# RS232_HIN232.net
KiCad netlist of a schematic drawn in Altium Designer
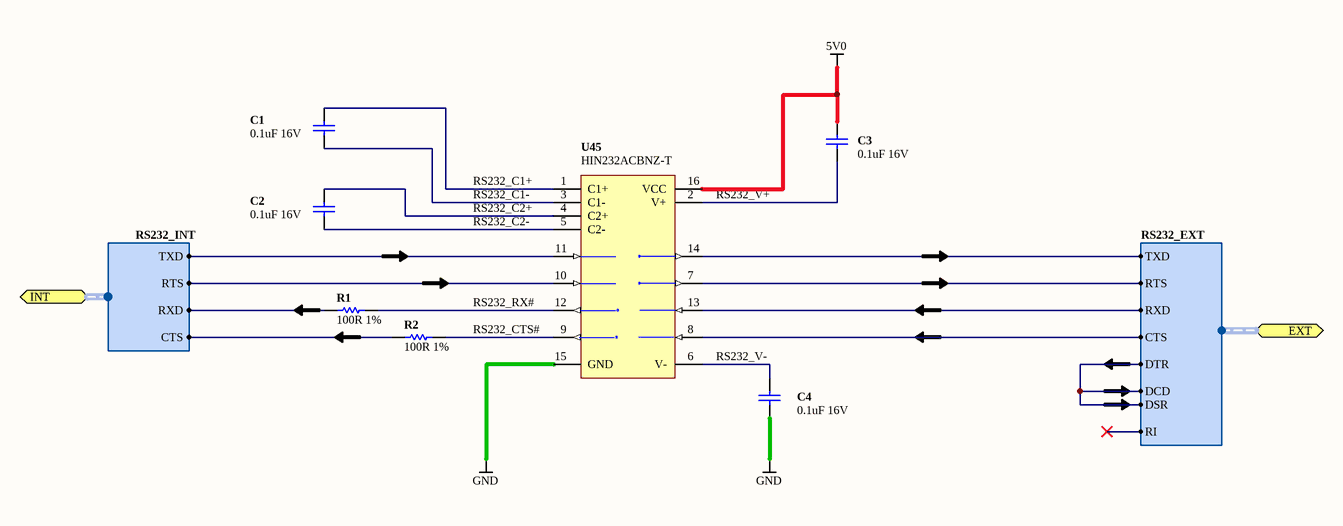
[diagram p0: RS232_HIN232.SchDoc]

(export (version "E")
  (design (tool "Eeschema 10.0.6"))
  (components
    (comp (ref "C1")
      (value "0.1uF 16V")
      (footprint "CAPC1005-STAR")
      (description "Capacitor, Ceramic, 0.1uF 10% 16V 0402 (1005) X7R")
      (fields (field (name "TOLERANCE") "10 %"))
      (libsource (lib "AltiumDesignLibrary") (part "CAP-NP"))
    )
    (comp (ref "C2")
      (value "0.1uF 16V")
      (footprint "CAPC1005-STAR")
      (description "Capacitor, Ceramic, 0.1uF 10% 16V 0402 (1005) X7R")
      (fields (field (name "TOLERANCE") "10 %"))
      (libsource (lib "AltiumDesignLibrary") (part "CAP-NP"))
    )
    (comp (ref "C3")
      (value "0.1uF 16V")
      (footprint "CAPC1005-STAR")
      (description "Capacitor, Ceramic, 0.1uF 10% 16V 0402 (1005) X7R")
      (fields (field (name "TOLERANCE") "10 %"))
      (libsource (lib "AltiumDesignLibrary") (part "CAP-NP"))
    )
    (comp (ref "C4")
      (value "0.1uF 16V")
      (footprint "CAPC1005-STAR")
      (description "Capacitor, Ceramic, 0.1uF 10% 16V 0402 (1005) X7R")
      (fields (field (name "TOLERANCE") "10 %"))
      (libsource (lib "AltiumDesignLibrary") (part "CAP-NP"))
    )
    (comp (ref "R1")
      (value "100R 1%")
      (footprint "RESC1005-STAR")
      (description "Resistor, 100R 1% 0402 (1005)")
      (fields (field (name "TOLERANCE") "1 %"))
      (libsource (lib "altium-import") (part "root_1_RES_"))
    )
    (comp (ref "R2")
      (value "100R 1%")
      (footprint "RESC1005-STAR")
      (description "Resistor, 100R 1% 0402 (1005)")
      (fields (field (name "TOLERANCE") "1 %"))
      (libsource (lib "altium-import") (part "root_1_RES_"))
    )
    (comp (ref "U45")
      (value "HIN232ACBNZ-T")
      (footprint "SOIC127P600-16")
      (description "HIN232ACBNZ-T 5V,  True RS-232 Transceivers")
      (libsource (lib "AltiumDesignLibrary") (part "MAX3232"))
    )
  )
  (nets
    (net (code "3") (name "/RS232_C1+") (class "Default")
      (node (ref "C1") (pin "1") (pinfunction "1_1") (pintype "passive"))
      (node (ref "U45") (pin "1") (pinfunction "C1+_1") (pintype "passive"))
    )
    (net (code "4") (name "/RS232_C1-") (class "Default")
      (node (ref "C1") (pin "2") (pinfunction "2_2") (pintype "passive"))
      (node (ref "U45") (pin "3") (pinfunction "C1-_3") (pintype "passive"))
    )
    (net (code "5") (name "/RS232_C2+") (class "Default")
      (node (ref "C2") (pin "1") (pinfunction "1_1") (pintype "passive"))
      (node (ref "U45") (pin "4") (pinfunction "C2+_4") (pintype "passive"))
    )
    (net (code "6") (name "/RS232_C2-") (class "Default")
      (node (ref "C2") (pin "2") (pinfunction "2_2") (pintype "passive"))
      (node (ref "U45") (pin "5") (pinfunction "C2-_5") (pintype "passive"))
    )
    (net (code "7") (name "/RS232_CTS#") (class "Default")
      (node (ref "R2") (pin "2") (pinfunction "2_2") (pintype "passive"))
      (node (ref "U45") (pin "9") (pinfunction "R2OUT_9") (pintype "output"))
    )
    (net (code "8") (name "/RS232_RX#") (class "Default")
      (node (ref "R1") (pin "2") (pinfunction "2_2") (pintype "passive"))
      (node (ref "U45") (pin "12") (pinfunction "R1OUT_12") (pintype "output"))
    )
    (net (code "9") (name "/RS232_V+") (class "Default")
      (node (ref "C3") (pin "2") (pinfunction "2_2") (pintype "passive"))
      (node (ref "U45") (pin "2") (pinfunction "V+_2") (pintype "power_in"))
    )
    (net (code "10") (name "/RS232_V-") (class "Default")
      (node (ref "C4") (pin "1") (pinfunction "1_1") (pintype "passive"))
      (node (ref "U45") (pin "6") (pinfunction "V-_6") (pintype "power_in"))
    )
    (net (code "13") (name "5V0") (class "Default")
      (node (ref "C3") (pin "1") (pinfunction "1_1") (pintype "passive"))
      (node (ref "U45") (pin "16") (pinfunction "VCC_16") (pintype "power_in"))
    )
    (net (code "14") (name "GND") (class "Default")
      (node (ref "C4") (pin "2") (pinfunction "2_2") (pintype "passive"))
      (node (ref "U45") (pin "15") (pinfunction "GND_15") (pintype "power_in"))
    )
    (net (code "15") (name "unconnected-(R1-Pad1)") (class "Default")
      (node (ref "R1") (pin "1") (pinfunction "1_1") (pintype "passive"))
    )
    (net (code "16") (name "unconnected-(R2-Pad1)") (class "Default")
      (node (ref "R2") (pin "1") (pinfunction "1_1") (pintype "passive"))
    )
    (net (code "17") (name "unconnected-(U45-R1IN-Pad13)") (class "Default")
      (node (ref "U45") (pin "13") (pinfunction "R1IN_13") (pintype "input"))
    )
    (net (code "18") (name "unconnected-(U45-R2IN-Pad8)") (class "Default")
      (node (ref "U45") (pin "8") (pinfunction "R2IN_8") (pintype "input"))
    )
    (net (code "19") (name "unconnected-(U45-T1IN-Pad11)") (class "Default")
      (node (ref "U45") (pin "11") (pinfunction "T1IN_11") (pintype "input"))
    )
    (net (code "20") (name "unconnected-(U45-T1OUT-Pad14)") (class "Default")
      (node (ref "U45") (pin "14") (pinfunction "T1OUT_14") (pintype "output"))
    )
    (net (code "21") (name "unconnected-(U45-T2IN-Pad10)") (class "Default")
      (node (ref "U45") (pin "10") (pinfunction "T2IN_10") (pintype "input"))
    )
    (net (code "22") (name "unconnected-(U45-T2OUT-Pad7)") (class "Default")
      (node (ref "U45") (pin "7") (pinfunction "T2OUT_7") (pintype "output"))
    )
  )
)
